# PC_Temperature_Controller.net
KiCad netlist of a schematic drawn in EAGLE
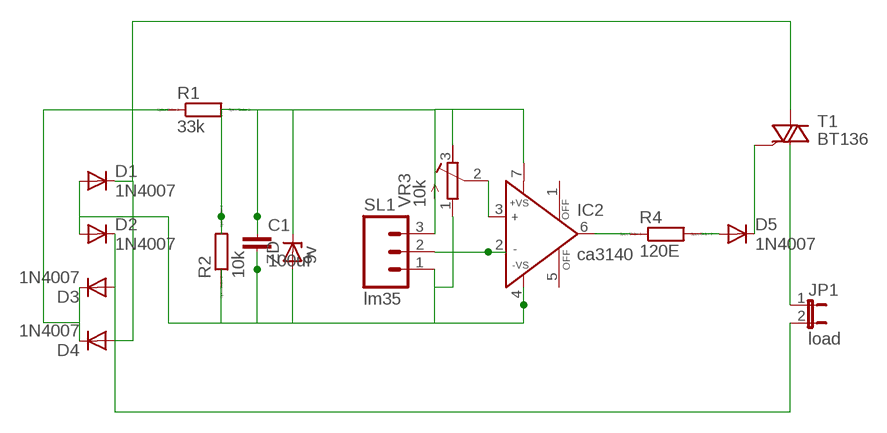
[diagram p0: schematic, sheet 1]

(export (version "E")
  (design (tool "Eeschema 10.0.6"))
  (components
    (comp (ref "C1")
      (value "100uf")
      (footprint "eagle-import:C2.5-4")
      (libsource (lib "eagle-import") (part "C2.5/4"))
    )
    (comp (ref "D1")
      (value "1N4007")
      (footprint "eagle-import:DO41-10")
      (libsource (lib "eagle-import") (part "1N4004"))
    )
    (comp (ref "D2")
      (value "1N4007")
      (footprint "eagle-import:DO41-10")
      (libsource (lib "eagle-import") (part "1N4004"))
    )
    (comp (ref "D3")
      (value "1N4007")
      (footprint "eagle-import:DO41-10")
      (libsource (lib "eagle-import") (part "1N4004"))
    )
    (comp (ref "D4")
      (value "1N4007")
      (footprint "eagle-import:DO41-10")
      (libsource (lib "eagle-import") (part "1N4004"))
    )
    (comp (ref "D5")
      (value "1N4007")
      (footprint "eagle-import:DO41-10")
      (libsource (lib "eagle-import") (part "1N4004"))
    )
    (comp (ref "IC2")
      (value "ca3140")
      (footprint "eagle-import:DIL08")
      (fields (field (name "MPN") "AD711BQ"))
      (libsource (lib "eagle-import") (part "AD711N"))
    )
    (comp (ref "JP1")
      (value "load")
      (footprint "eagle-import:JP1")
      (libsource (lib "eagle-import") (part "JP1E"))
    )
    (comp (ref "R1")
      (value "33k")
      (footprint "eagle-import:0204_7")
      (libsource (lib "eagle-import") (part "R0204/7"))
    )
    (comp (ref "R2")
      (value "10k")
      (footprint "eagle-import:0204_7")
      (libsource (lib "eagle-import") (part "R0204/7"))
    )
    (comp (ref "R4")
      (value "120E")
      (footprint "eagle-import:0204_7")
      (libsource (lib "eagle-import") (part "R0204/7"))
    )
    (comp (ref "SL1")
      (value "lm35")
      (footprint "eagle-import:03P")
      (libsource (lib "eagle-import") (part "M03"))
    )
    (comp (ref "T1")
      (value "BT136")
      (footprint "eagle-import:TO220AB")
      (libsource (lib "eagle-import") (part "BT136"))
    )
    (comp (ref "VR3")
      (value "10k")
      (footprint "eagle-import:RTRIM64P")
      (libsource (lib "eagle-import") (part "R-TRIMM64P"))
    )
    (comp (ref "ZD")
      (value "9v")
      (footprint "eagle-import:DO34Z7")
      (libsource (lib "eagle-import") (part "ZENER-DIODEDO34-7"))
    )
  )
  (nets
    (net (code "1") (name "Net-(D2-PadC)") (class "Default")
      (node (ref "D2") (pin "C") (pinfunction "C_C") (pintype "passive"))
      (node (ref "D3") (pin "A") (pinfunction "A_A") (pintype "passive"))
      (node (ref "JP1") (pin "2") (pinfunction "2_2") (pintype "passive"))
    )
    (net (code "2") (name "Net-(D3-PadC)") (class "Default")
      (node (ref "D3") (pin "C") (pinfunction "C_C") (pintype "passive"))
      (node (ref "D4") (pin "C") (pinfunction "C_C") (pintype "passive"))
      (node (ref "R1") (pin "1") (pinfunction "1_1") (pintype "passive"))
    )
    (net (code "3") (name "Net-(D5-PadA)") (class "Default")
      (node (ref "D5") (pin "A") (pinfunction "A_A") (pintype "passive"))
      (node (ref "R4") (pin "2") (pinfunction "2_2") (pintype "passive"))
    )
    (net (code "4") (name "Net-(IC2-+VS)") (class "Default")
      (node (ref "C1") (pin "1") (pinfunction "1_1") (pintype "passive"))
      (node (ref "IC2") (pin "7") (pinfunction "+VS_7") (pintype "input"))
      (node (ref "R1") (pin "2") (pinfunction "2_2") (pintype "passive"))
      (node (ref "R2") (pin "2") (pinfunction "2_2") (pintype "passive"))
      (node (ref "SL1") (pin "3") (pinfunction "3_3") (pintype "passive"))
      (node (ref "VR3") (pin "3") (pinfunction "A_3") (pintype "passive"))
      (node (ref "ZD") (pin "C") (pinfunction "C_C") (pintype "passive"))
    )
    (net (code "5") (name "Net-(IC2--VS)") (class "Default")
      (node (ref "C1") (pin "2") (pinfunction "2_2") (pintype "passive"))
      (node (ref "D1") (pin "A") (pinfunction "A_A") (pintype "passive"))
      (node (ref "D2") (pin "A") (pinfunction "A_A") (pintype "passive"))
      (node (ref "IC2") (pin "4") (pinfunction "-VS_4") (pintype "input"))
      (node (ref "R2") (pin "1") (pinfunction "1_1") (pintype "passive"))
      (node (ref "SL1") (pin "1") (pinfunction "1_1") (pintype "passive"))
      (node (ref "VR3") (pin "1") (pinfunction "E_1") (pintype "passive"))
      (node (ref "ZD") (pin "A") (pinfunction "A_A") (pintype "passive"))
    )
    (net (code "6") (name "Net-(IC2-IN+)") (class "Default")
      (node (ref "IC2") (pin "3") (pinfunction "IN+_3") (pintype "input"))
      (node (ref "VR3") (pin "2") (pinfunction "S_2") (pintype "passive"))
    )
    (net (code "7") (name "Net-(IC2-IN-)") (class "Default")
      (node (ref "IC2") (pin "2") (pinfunction "IN-_2") (pintype "input"))
      (node (ref "SL1") (pin "2") (pinfunction "2_2") (pintype "passive"))
    )
    (net (code "8") (name "Net-(IC2-OUT)") (class "Default")
      (node (ref "IC2") (pin "6") (pinfunction "OUT_6") (pintype "output"))
      (node (ref "R4") (pin "1") (pinfunction "1_1") (pintype "passive"))
    )
    (net (code "9") (name "Net-(T1-A1)") (class "Default")
      (node (ref "JP1") (pin "1") (pinfunction "1_1") (pintype "passive"))
      (node (ref "T1") (pin "1") (pinfunction "A1_1") (pintype "passive"))
    )
    (net (code "10") (name "Net-(T1-A2)") (class "Default")
      (node (ref "D1") (pin "C") (pinfunction "C_C") (pintype "passive"))
      (node (ref "D4") (pin "A") (pinfunction "A_A") (pintype "passive"))
      (node (ref "T1") (pin "2") (pinfunction "A2_2") (pintype "passive"))
    )
    (net (code "11") (name "Net-(T1-G)") (class "Default")
      (node (ref "D5") (pin "C") (pinfunction "C_C") (pintype "passive"))
      (node (ref "T1") (pin "3") (pinfunction "G_3") (pintype "passive"))
    )
    (net (code "12") (name "unconnected-(IC2-OFF-Pad1)") (class "Default")
      (node (ref "IC2") (pin "1") (pinfunction "OFF_1") (pintype "passive"))
    )
    (net (code "13") (name "unconnected-(IC2-OFF-Pad5)") (class "Default")
      (node (ref "IC2") (pin "5") (pinfunction "OFF_5") (pintype "passive"))
    )
  )
)
